# Log_and_Anti-Log_Converters_2.net
KiCad netlist of a schematic drawn in Altium Designer
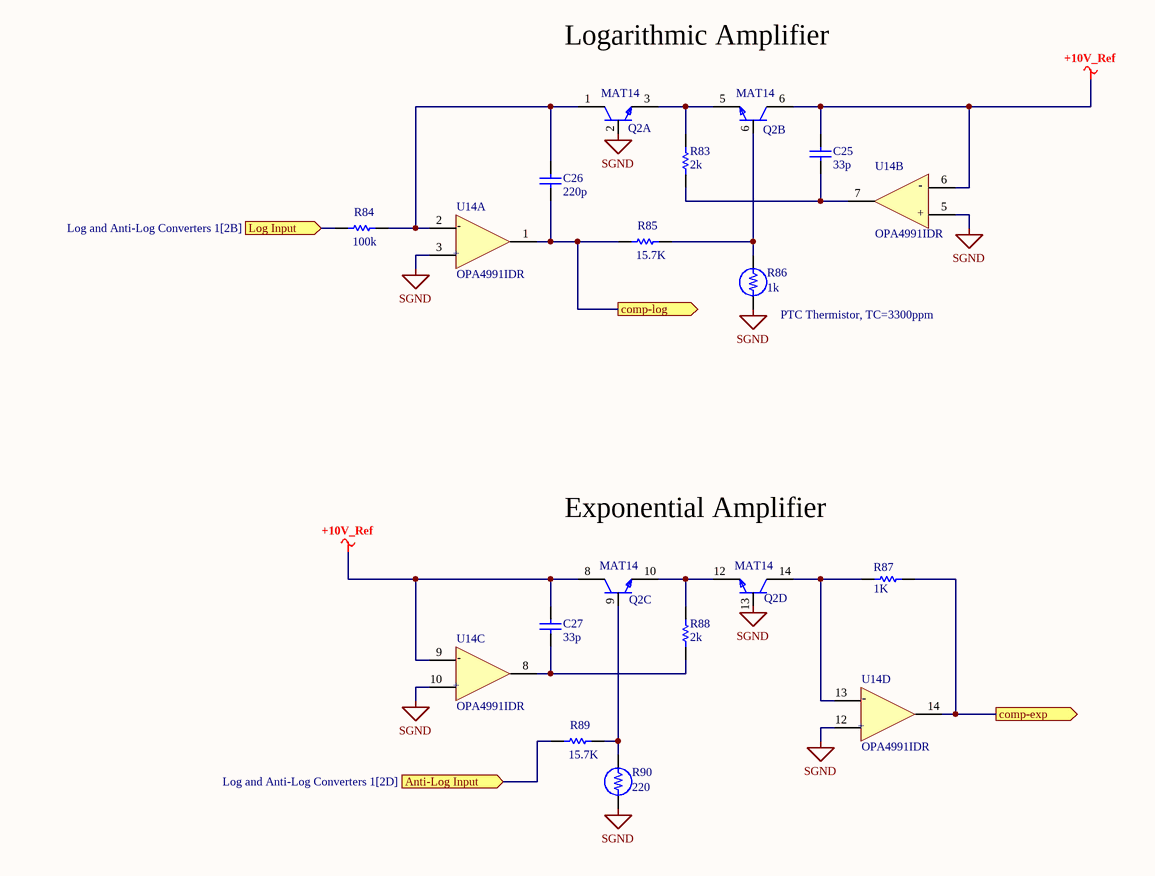
[diagram p0: Log and Anti-Log Converters 2.SchDoc]

(export (version "E")
  (design (tool "Eeschema 10.0.6"))
  (components
    (comp (ref "C25")
      (value "33p")
      (description "Capacitor")
      (libsource (lib "Simulation Generic Components") (part "Capacitor"))
    )
    (comp (ref "C26")
      (value "220p")
      (description "Capacitor")
      (libsource (lib "Simulation Generic Components") (part "Capacitor"))
    )
    (comp (ref "C27")
      (value "33p")
      (description "Capacitor")
      (libsource (lib "Simulation Generic Components") (part "Capacitor"))
    )
    (comp (ref "Q2")
      (value "MAT14")
      (footprint "FP-R-14-IPC_B")
      (description "TRANS 4NPN 40V 0.03A 14SO")
      (libsource (lib "") (part "MAT14ARZ_1"))
    )
    (comp (ref "R83")
      (value "2k")
      (description "Resistor")
      (libsource (lib "Simulation Generic Components") (part "Resistor"))
    )
    (comp (ref "R84")
      (value "100k")
      (description "Resistor")
      (libsource (lib "Simulation Generic Components") (part "Resistor"))
    )
    (comp (ref "R85")
      (value "15.7K")
      (description "Resistor")
      (libsource (lib "Simulation Generic Components") (part "Resistor"))
    )
    (comp (ref "R86") (value "1k") (libsource (lib "DRC") (part "PTC Thermistor")))
    (comp (ref "R87")
      (value "1K")
      (description "Resistor")
      (libsource (lib "Simulation Generic Components") (part "Resistor"))
    )
    (comp (ref "R88")
      (value "2k")
      (description "Resistor")
      (libsource (lib "Simulation Generic Components") (part "Resistor"))
    )
    (comp (ref "R89")
      (value "15.7K")
      (description "Resistor")
      (libsource (lib "Simulation Generic Components") (part "Resistor"))
    )
    (comp (ref "R90") (value "220") (libsource (lib "DRC") (part "PTC Thermistor")))
    (comp (ref "U14")
      (value "OPA4991IDR")
      (footprint "FP-D0014A-IPC_B")
      (description "40-V, DUAL 4.5MHZ, RAIL-TO-RAIL")
      (libsource (lib "DRC") (part "OPA4991IDR"))
    )
  )
  (nets
    (net (code "1") (name "+10V_Ref") (class "Default")
      (node (ref "C25") (pin "2") (pinfunction "2_2") (pintype "passive"))
      (node (ref "C27") (pin "2") (pinfunction "2_2") (pintype "passive"))
      (node (ref "Q2") (pin "6") (pinfunction "C2_6") (pintype "passive"))
      (node (ref "Q2") (pin "8") (pinfunction "C3_8") (pintype "passive"))
      (node (ref "U14") (pin "6") (pinfunction "IN2-_6") (pintype "tri_state"))
      (node (ref "U14") (pin "9") (pinfunction "IN3-_9") (pintype "tri_state"))
    )
    (net (code "2") (name "/Anti-Log Input") (class "Default")
      (node (ref "R89") (pin "2") (pinfunction "2_2") (pintype "passive"))
    )
    (net (code "3") (name "/Log Input") (class "Default")
      (node (ref "R84") (pin "2") (pinfunction "2_2") (pintype "passive"))
    )
    (net (code "4") (name "/comp-exp") (class "Default")
      (node (ref "R87") (pin "2") (pinfunction "2_2") (pintype "passive"))
      (node (ref "U14") (pin "14") (pinfunction "OUT4_14") (pintype "passive"))
    )
    (net (code "5") (name "/comp-log") (class "Default")
      (node (ref "C26") (pin "1") (pinfunction "1_1") (pintype "passive"))
      (node (ref "R85") (pin "2") (pinfunction "2_2") (pintype "passive"))
      (node (ref "U14") (pin "1") (pinfunction "OUT1_1") (pintype "passive"))
    )
    (net (code "6") (name "Net-(Q2A-C1)") (class "Default")
      (node (ref "C26") (pin "2") (pinfunction "2_2") (pintype "passive"))
      (node (ref "Q2") (pin "1") (pinfunction "C1_1") (pintype "passive"))
      (node (ref "R84") (pin "1") (pinfunction "1_1") (pintype "passive"))
      (node (ref "U14") (pin "2") (pinfunction "IN1-_2") (pintype "tri_state"))
    )
    (net (code "7") (name "Net-(Q2A-E1)") (class "Default")
      (node (ref "Q2") (pin "3") (pinfunction "E1_3") (pintype "passive"))
      (node (ref "Q2") (pin "5") (pinfunction "E2_5") (pintype "passive"))
      (node (ref "R83") (pin "2") (pinfunction "2_2") (pintype "passive"))
    )
    (net (code "8") (name "Net-(Q2B-B2)") (class "Default")
      (node (ref "Q2") (pin "6") (pinfunction "B2_6") (pintype "passive"))
      (node (ref "R85") (pin "1") (pinfunction "1_1") (pintype "passive"))
      (node (ref "R86") (pin "2") (pinfunction "2_2") (pintype "passive"))
    )
    (net (code "9") (name "Net-(Q2C-B3)") (class "Default")
      (node (ref "Q2") (pin "9") (pinfunction "B3_9") (pintype "passive"))
      (node (ref "R89") (pin "1") (pinfunction "1_1") (pintype "passive"))
      (node (ref "R90") (pin "2") (pinfunction "2_2") (pintype "passive"))
    )
    (net (code "10") (name "Net-(Q2C-E3)") (class "Default")
      (node (ref "Q2") (pin "10") (pinfunction "E3_10") (pintype "passive"))
      (node (ref "Q2") (pin "12") (pinfunction "E4_12") (pintype "passive"))
      (node (ref "R88") (pin "2") (pinfunction "2_2") (pintype "passive"))
    )
    (net (code "11") (name "Net-(Q2D-C4)") (class "Default")
      (node (ref "Q2") (pin "14") (pinfunction "C4_14") (pintype "passive"))
      (node (ref "R87") (pin "1") (pinfunction "1_1") (pintype "passive"))
      (node (ref "U14") (pin "13") (pinfunction "IN4-_13") (pintype "tri_state"))
    )
    (net (code "12") (name "Net-(U14B-OUT2)") (class "Default")
      (node (ref "C25") (pin "1") (pinfunction "1_1") (pintype "passive"))
      (node (ref "R83") (pin "1") (pinfunction "1_1") (pintype "passive"))
      (node (ref "U14") (pin "7") (pinfunction "OUT2_7") (pintype "passive"))
    )
    (net (code "13") (name "Net-(U14C-OUT3)") (class "Default")
      (node (ref "C27") (pin "1") (pinfunction "1_1") (pintype "passive"))
      (node (ref "R88") (pin "1") (pinfunction "1_1") (pintype "passive"))
      (node (ref "U14") (pin "8") (pinfunction "OUT3_8") (pintype "passive"))
    )
    (net (code "14") (name "SGND") (class "Default")
      (node (ref "Q2") (pin "13") (pinfunction "B4_13") (pintype "passive"))
      (node (ref "Q2") (pin "2") (pinfunction "B1_2") (pintype "passive"))
      (node (ref "R86") (pin "1") (pinfunction "1_1") (pintype "passive"))
      (node (ref "R90") (pin "1") (pinfunction "1_1") (pintype "passive"))
      (node (ref "U14") (pin "10") (pinfunction "IN3+_10") (pintype "tri_state"))
      (node (ref "U14") (pin "12") (pinfunction "IN4+_12") (pintype "tri_state"))
      (node (ref "U14") (pin "3") (pinfunction "IN1+_3") (pintype "tri_state"))
      (node (ref "U14") (pin "5") (pinfunction "IN2+_5") (pintype "tri_state"))
    )
  )
)
